# WL-CONTROL.net
KiCad netlist of a schematic drawn in Altium Designer
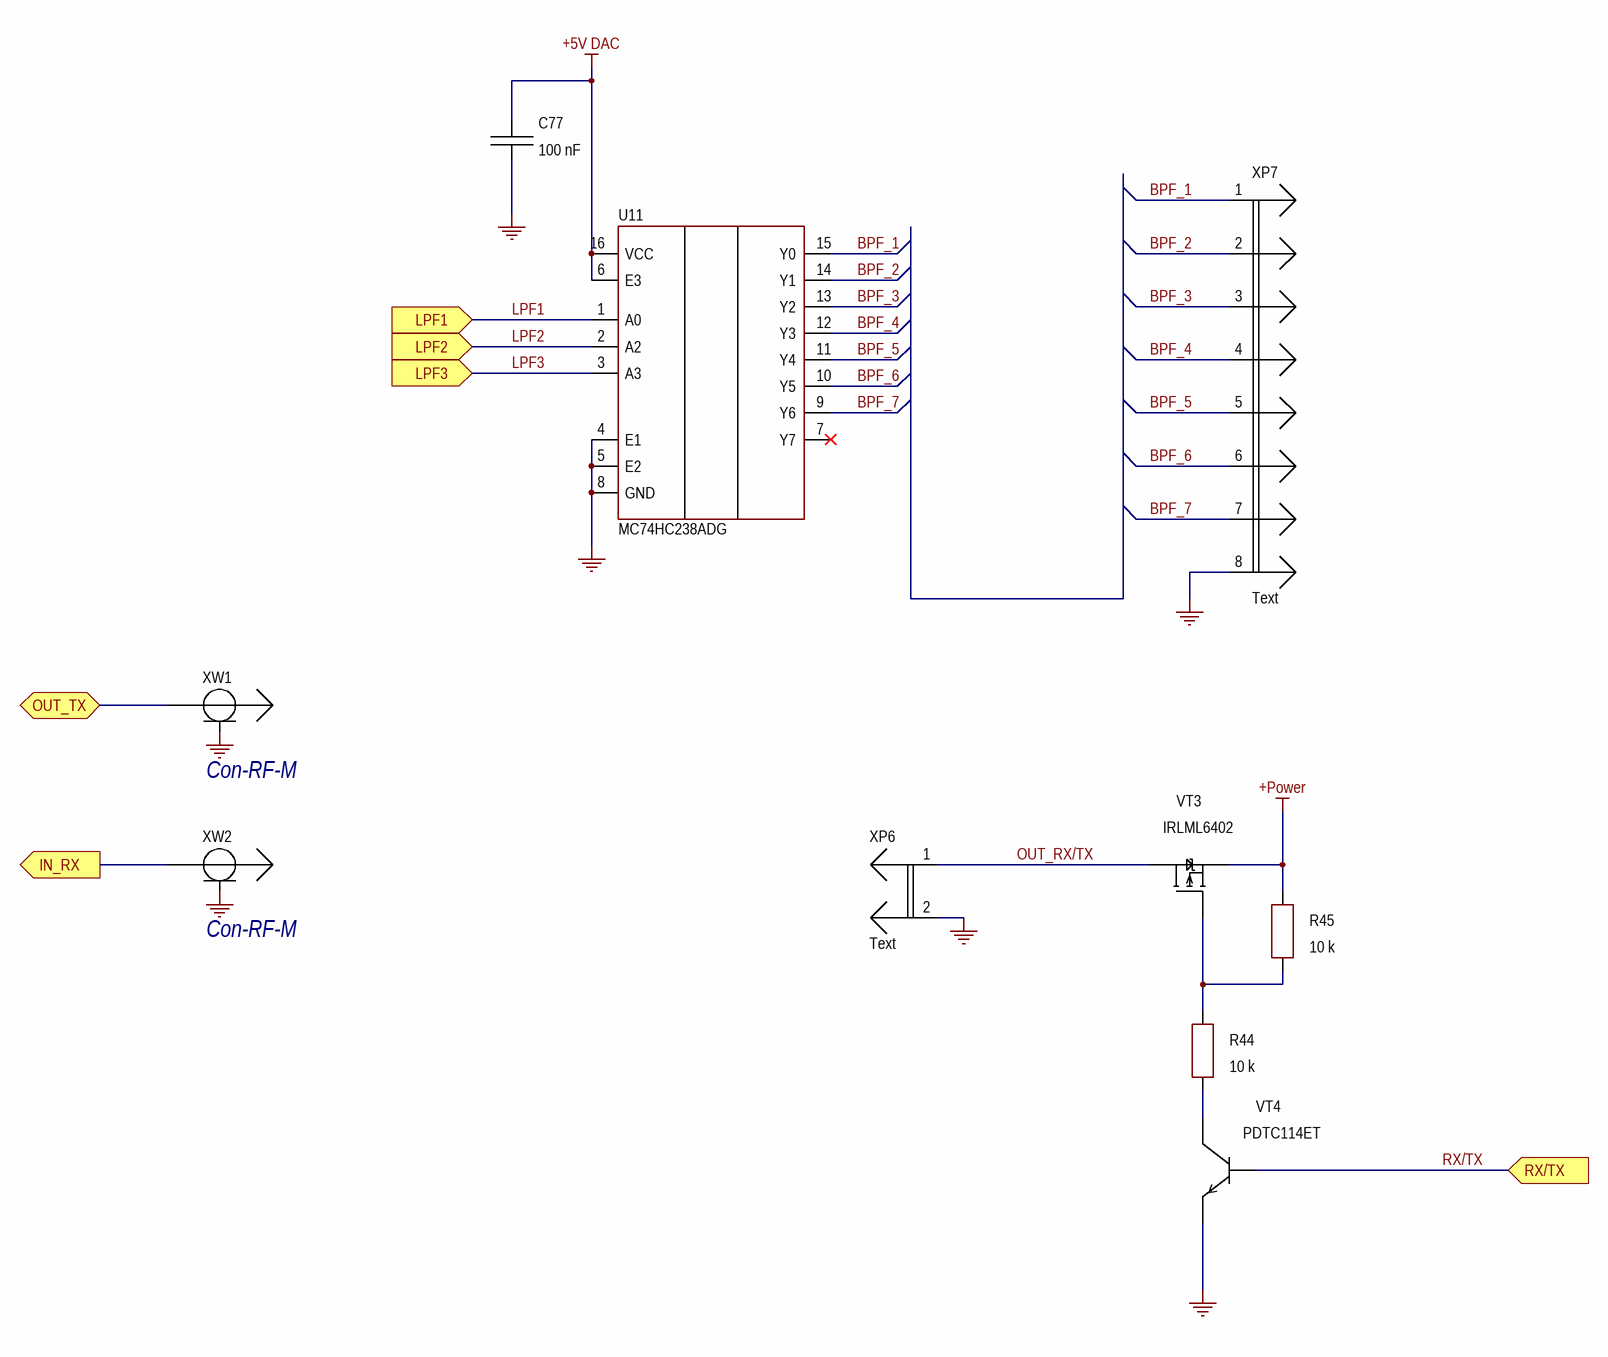
[diagram p0: WL-CONTROL.SchDoc]

(export (version "E")
  (design (tool "Eeschema 10.0.6"))
  (components
    (comp (ref "C77")
      (value "100 nF")
      (footprint "C-0805-0.95")
      (fields
        (field (name "MANUFACTURER") "Yageo")
        (field (name "PART NUMBER") "CC0805KRX7R9BB104")
        (field (name "TOLERANCE") "±10%")
      )
      (libsource (lib "GOST") (part "Capacitor"))
    )
    (comp (ref "R44")
      (value "10 k")
      (footprint "R-0805")
      (fields
        (field (name "MANUFACTURER") "Yageo")
        (field (name "PART NUMBER") "RC0805JR-0710KL")
        (field (name "POWER") "0,125 W")
      )
      (libsource (lib "GOST") (part "Resistor"))
    )
    (comp (ref "R45")
      (value "10 k")
      (footprint "R-0805")
      (fields
        (field (name "MANUFACTURER") "Yageo")
        (field (name "PART NUMBER") "RC0805JR-0710KL")
        (field (name "POWER") "0,125 W")
      )
      (libsource (lib "GOST") (part "Resistor"))
    )
    (comp (ref "U11")
      (value "MC74HC238ADG")
      (footprint "SOIC-16")
      (description "IC DECODER/DEMUX 1X3:8")
      (fields (field (name "MANUFACTURER") "ON Semiconductor"))
      (libsource (lib "GOST") (part "MC74HC238ADG"))
    )
    (comp (ref "VT3")
      (value "IRLML6402")
      (footprint "SOT-23")
      (fields
        (field (name "PART NUMBER") "IRLML6402TRPBF")
        (field (name "MANUFACTURER") "Infineon Technologies")
      )
      (libsource (lib "GOST") (part "MOSFET-P"))
    )
    (comp (ref "VT4")
      (value "PDTC114ET")
      (footprint "SOT-23")
      (fields (field (name "PART NUMBER") "PDTC114ET,215") (field (name "MANUFACTURER") "Nexperia USA Inc."))
      (libsource (lib "GOST") (part "BJT-NPN"))
    )
    (comp (ref "XP6")
      (value "Text")
      (footprint "61900211121")
      (fields (field (name "PART NUMBER") "61900211121") (field (name "MANUFACTURER") "Würth Elektronik"))
      (libsource (lib "GOST") (part "Con-2-M"))
    )
    (comp (ref "XP7")
      (value "Text")
      (footprint "CON PLD-8")
      (fields
        (field (name "PART NUMBER") "PLD-8")
        (field (name "MANUFACTURER") "Connfly Electronic Co., Ltd.")
      )
      (libsource (lib "GOST") (part "Con-8-M"))
    )
    (comp (ref "XW1")
      (value "Con-RF-M")
      (footprint "A-1JB")
      (fields (field (name "PART NUMBER") "A-1JB") (field (name "MANUFACTURER") "Amphenol RF"))
      (libsource (lib "GOST") (part "Con-RF-M"))
    )
    (comp (ref "XW2")
      (value "Con-RF-M")
      (footprint "A-1JB")
      (fields (field (name "PART NUMBER") "A-1JB") (field (name "MANUFACTURER") "Amphenol RF"))
      (libsource (lib "GOST") (part "Con-RF-M"))
    )
  )
  (nets
    (net (code "1") (name "+5V DAC") (class "Default")
      (node (ref "C77") (pin "1") (pinfunction "1_1") (pintype "passive"))
      (node (ref "U11") (pin "16") (pinfunction "VCC_16") (pintype "passive"))
      (node (ref "U11") (pin "6") (pinfunction "E3_6") (pintype "passive"))
    )
    (net (code "2") (name "+Power") (class "Default")
      (node (ref "R45") (pin "2") (pinfunction "2_2") (pintype "passive"))
      (node (ref "VT3") (pin "2") (pinfunction "S_2") (pintype "passive"))
    )
    (net (code "3") (name "/BPF_1") (class "Default")
      (node (ref "U11") (pin "15") (pinfunction "Y0_15") (pintype "passive"))
      (node (ref "XP7") (pin "1") (pintype "passive"))
    )
    (net (code "4") (name "/BPF_2") (class "Default")
      (node (ref "U11") (pin "14") (pinfunction "Y1_14") (pintype "passive"))
      (node (ref "XP7") (pin "2") (pintype "passive"))
    )
    (net (code "5") (name "/BPF_3") (class "Default")
      (node (ref "U11") (pin "13") (pinfunction "Y2_13") (pintype "passive"))
      (node (ref "XP7") (pin "3") (pintype "passive"))
    )
    (net (code "6") (name "/BPF_4") (class "Default")
      (node (ref "U11") (pin "12") (pinfunction "Y3_12") (pintype "passive"))
      (node (ref "XP7") (pin "4") (pintype "passive"))
    )
    (net (code "7") (name "/BPF_5") (class "Default")
      (node (ref "U11") (pin "11") (pinfunction "Y4_11") (pintype "passive"))
      (node (ref "XP7") (pin "5") (pintype "passive"))
    )
    (net (code "8") (name "/BPF_6") (class "Default")
      (node (ref "U11") (pin "10") (pinfunction "Y5_10") (pintype "passive"))
      (node (ref "XP7") (pin "6") (pintype "passive"))
    )
    (net (code "9") (name "/BPF_7") (class "Default")
      (node (ref "U11") (pin "9") (pinfunction "Y6_9") (pintype "passive"))
      (node (ref "XP7") (pin "7") (pintype "passive"))
    )
    (net (code "10") (name "/IN_RX") (class "Default") (node (ref "XW2") (pin "1") (pintype "passive")))
    (net (code "11") (name "/LPF1") (class "Default")
      (node (ref "U11") (pin "1") (pinfunction "A0_1") (pintype "passive"))
    )
    (net (code "12") (name "/LPF2") (class "Default")
      (node (ref "U11") (pin "2") (pinfunction "A2_2") (pintype "passive"))
    )
    (net (code "13") (name "/LPF3") (class "Default")
      (node (ref "U11") (pin "3") (pinfunction "A3_3") (pintype "passive"))
    )
    (net (code "14") (name "/OUT_RX{slash}TX") (class "Default")
      (node (ref "VT3") (pin "3") (pinfunction "D_3") (pintype "passive"))
      (node (ref "XP6") (pin "1") (pintype "passive"))
    )
    (net (code "15") (name "/OUT_TX") (class "Default") (node (ref "XW1") (pin "1") (pintype "passive")))
    (net (code "16") (name "/RX{slash}TX") (class "Default")
      (node (ref "VT4") (pin "1") (pinfunction "1_1") (pintype "passive"))
    )
    (net (code "17") (name "GND") (class "Default")
      (node (ref "C77") (pin "2") (pinfunction "2_2") (pintype "passive"))
      (node (ref "U11") (pin "4") (pinfunction "E1_4") (pintype "passive"))
      (node (ref "U11") (pin "5") (pinfunction "E2_5") (pintype "passive"))
      (node (ref "U11") (pin "8") (pinfunction "GND_8") (pintype "passive"))
      (node (ref "VT4") (pin "2") (pinfunction "2_2") (pintype "passive"))
      (node (ref "XP6") (pin "2") (pintype "passive"))
      (node (ref "XP7") (pin "8") (pintype "passive"))
      (node (ref "XW1") (pin "2") (pintype "passive"))
      (node (ref "XW2") (pin "2") (pintype "passive"))
    )
    (net (code "18") (name "Net-(R44-Pad1)") (class "Default")
      (node (ref "R44") (pin "1") (pinfunction "1_1") (pintype "passive"))
      (node (ref "VT4") (pin "3") (pinfunction "3_3") (pintype "passive"))
    )
    (net (code "19") (name "Net-(VT3-G)") (class "Default")
      (node (ref "R44") (pin "2") (pinfunction "2_2") (pintype "passive"))
      (node (ref "R45") (pin "1") (pinfunction "1_1") (pintype "passive"))
      (node (ref "VT3") (pin "1") (pinfunction "G_1") (pintype "passive"))
    )
    (net (code "20") (name "unconnected-(U11-Y7-Pad7)") (class "Default")
      (node (ref "U11") (pin "7") (pinfunction "Y7_7") (pintype "passive+no_connect"))
    )
  )
)
